# 05021002_GPIO_s.net
KiCad netlist of a schematic drawn in Altium Designer
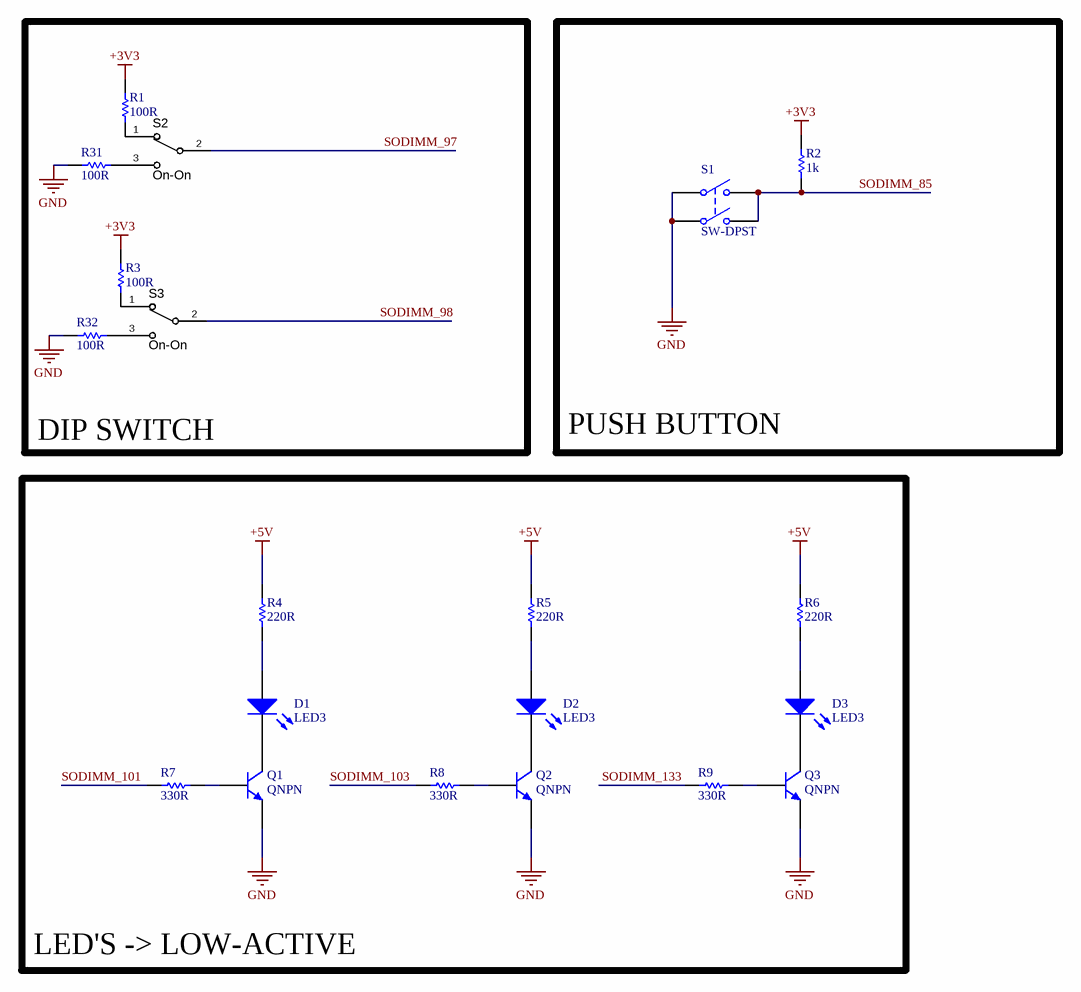
[diagram p0: 05021002_GPIO's.SchDoc]

(export (version "E")
  (design (tool "Eeschema 10.0.6"))
  (components
    (comp (ref "D1")
      (value "LED3")
      (footprint "LED-0805-K")
      (description "Typical BLUE SiC LED")
      (fields (field (name "PUBLISHER") "Altium Limited"))
      (libsource (lib "Miscellaneous Devices") (part "LED3"))
    )
    (comp (ref "D2")
      (value "LED3")
      (footprint "LED-0805-K")
      (description "Typical BLUE SiC LED")
      (fields (field (name "PUBLISHER") "Altium Limited"))
      (libsource (lib "Miscellaneous Devices") (part "LED3"))
    )
    (comp (ref "D3")
      (value "LED3")
      (footprint "LED-0805-K")
      (description "Typical BLUE SiC LED")
      (fields (field (name "PUBLISHER") "Altium Limited"))
      (libsource (lib "Miscellaneous Devices") (part "LED3"))
    )
    (comp (ref "Q1")
      (value "QNPN")
      (footprint "SOT-23")
      (description "NPN Bipolar Transistor")
      (fields (field (name "PUBLISHER") "Altium Limited"))
      (libsource (lib "Miscellaneous Devices") (part "QNPN"))
    )
    (comp (ref "Q2")
      (value "QNPN")
      (footprint "SOT-23")
      (description "NPN Bipolar Transistor")
      (fields (field (name "PUBLISHER") "Altium Limited"))
      (libsource (lib "Miscellaneous Devices") (part "QNPN"))
    )
    (comp (ref "Q3")
      (value "QNPN")
      (footprint "SOT-23")
      (description "NPN Bipolar Transistor")
      (fields (field (name "PUBLISHER") "Altium Limited"))
      (libsource (lib "Miscellaneous Devices") (part "QNPN"))
    )
    (comp (ref "R1")
      (value "100R")
      (footprint "0805")
      (libsource (lib "resistor_smd_gen") (part "resistor_gen"))
    )
    (comp (ref "R2")
      (value "1k")
      (footprint "0805")
      (libsource (lib "resistor_smd_gen") (part "resistor_gen"))
    )
    (comp (ref "R3")
      (value "100R")
      (footprint "0805")
      (libsource (lib "resistor_smd_gen") (part "resistor_gen"))
    )
    (comp (ref "R4")
      (value "220R")
      (footprint "0805")
      (libsource (lib "resistor_smd_gen") (part "resistor_gen"))
    )
    (comp (ref "R5")
      (value "220R")
      (footprint "0805")
      (libsource (lib "resistor_smd_gen") (part "resistor_gen"))
    )
    (comp (ref "R6")
      (value "220R")
      (footprint "0805")
      (libsource (lib "resistor_smd_gen") (part "resistor_gen"))
    )
    (comp (ref "R7")
      (value "330R")
      (footprint "0805")
      (libsource (lib "resistor_smd_gen") (part "resistor_gen"))
    )
    (comp (ref "R8")
      (value "330R")
      (footprint "0805")
      (libsource (lib "resistor_smd_gen") (part "resistor_gen"))
    )
    (comp (ref "R9")
      (value "330R")
      (footprint "0805")
      (libsource (lib "resistor_smd_gen") (part "resistor_gen"))
    )
    (comp (ref "R31")
      (value "100R")
      (footprint "0805")
      (libsource (lib "resistor_smd_gen") (part "resistor_gen"))
    )
    (comp (ref "R32")
      (value "100R")
      (footprint "0805")
      (libsource (lib "resistor_smd_gen") (part "resistor_gen"))
    )
    (comp (ref "S1")
      (value "SW-DPST")
      (footprint "430182080816")
      (description "Double-Pole, Single-Throw Switch")
      (fields (field (name "PUBLISHER") "Altium Limited"))
      (libsource (lib "Miscellaneous Devices") (part "SW-DPST"))
    )
    (comp (ref "S2")
      (value "ON-ON")
      (footprint "SWITCH_SPDT_SLIDER")
      (description "Switch THD vertical toggle SPDT")
      (fields (field (name "SWITCH FUNCTION") "On-On"))
      (libsource (lib "PBL - Switches") (part "SW_THD_SPDT_On-On"))
    )
    (comp (ref "S3")
      (value "ON-ON")
      (footprint "SWITCH_SPDT_SLIDER")
      (description "Switch THD vertical toggle SPDT")
      (fields (field (name "SWITCH FUNCTION") "On-On"))
      (libsource (lib "PBL - Switches") (part "SW_THD_SPDT_On-On"))
    )
  )
  (nets
    (net (code "1") (name "+3V3") (class "Default")
      (node (ref "R1") (pin "2") (pinfunction "2_2") (pintype "passive"))
      (node (ref "R2") (pin "2") (pinfunction "2_2") (pintype "passive"))
      (node (ref "R3") (pin "2") (pinfunction "2_2") (pintype "passive"))
    )
    (net (code "2") (name "+5V") (class "Default")
      (node (ref "R4") (pin "2") (pinfunction "2_2") (pintype "passive"))
      (node (ref "R5") (pin "2") (pinfunction "2_2") (pintype "passive"))
      (node (ref "R6") (pin "2") (pinfunction "2_2") (pintype "passive"))
    )
    (net (code "3") (name "/SODIMM_85") (class "Default")
      (node (ref "R2") (pin "1") (pinfunction "1_1") (pintype "passive"))
      (node (ref "S1") (pin "2") (pinfunction "NO1_2") (pintype "passive"))
      (node (ref "S1") (pin "4") (pinfunction "NO2_4") (pintype "passive"))
    )
    (net (code "4") (name "/SODIMM_97") (class "Default")
      (node (ref "S2") (pin "2") (pinfunction "2_2") (pintype "passive"))
    )
    (net (code "5") (name "/SODIMM_98") (class "Default")
      (node (ref "S3") (pin "2") (pinfunction "2_2") (pintype "passive"))
    )
    (net (code "6") (name "/SODIMM_101") (class "Default")
      (node (ref "R7") (pin "1") (pinfunction "1_1") (pintype "passive"))
    )
    (net (code "7") (name "/SODIMM_103") (class "Default")
      (node (ref "R8") (pin "1") (pinfunction "1_1") (pintype "passive"))
    )
    (net (code "8") (name "/SODIMM_133") (class "Default")
      (node (ref "R9") (pin "1") (pinfunction "1_1") (pintype "passive"))
    )
    (net (code "9") (name "GND") (class "Default")
      (node (ref "Q1") (pin "3") (pinfunction "E_3") (pintype "passive"))
      (node (ref "Q2") (pin "3") (pinfunction "E_3") (pintype "passive"))
      (node (ref "Q3") (pin "3") (pinfunction "E_3") (pintype "passive"))
      (node (ref "R31") (pin "2") (pinfunction "2_2") (pintype "passive"))
      (node (ref "R32") (pin "2") (pinfunction "2_2") (pintype "passive"))
      (node (ref "S1") (pin "1") (pinfunction "COMMON1_1") (pintype "passive"))
      (node (ref "S1") (pin "3") (pinfunction "COMMON2_3") (pintype "passive"))
    )
    (net (code "10") (name "Net-(D1-A)") (class "Default")
      (node (ref "D1") (pin "1") (pinfunction "A_1") (pintype "passive"))
      (node (ref "R4") (pin "1") (pinfunction "1_1") (pintype "passive"))
    )
    (net (code "11") (name "Net-(D1-K)") (class "Default")
      (node (ref "D1") (pin "2") (pinfunction "K_2") (pintype "passive"))
      (node (ref "Q1") (pin "1") (pinfunction "C_1") (pintype "passive"))
    )
    (net (code "12") (name "Net-(D2-A)") (class "Default")
      (node (ref "D2") (pin "1") (pinfunction "A_1") (pintype "passive"))
      (node (ref "R5") (pin "1") (pinfunction "1_1") (pintype "passive"))
    )
    (net (code "13") (name "Net-(D2-K)") (class "Default")
      (node (ref "D2") (pin "2") (pinfunction "K_2") (pintype "passive"))
      (node (ref "Q2") (pin "1") (pinfunction "C_1") (pintype "passive"))
    )
    (net (code "14") (name "Net-(D3-A)") (class "Default")
      (node (ref "D3") (pin "1") (pinfunction "A_1") (pintype "passive"))
      (node (ref "R6") (pin "1") (pinfunction "1_1") (pintype "passive"))
    )
    (net (code "15") (name "Net-(D3-K)") (class "Default")
      (node (ref "D3") (pin "2") (pinfunction "K_2") (pintype "passive"))
      (node (ref "Q3") (pin "1") (pinfunction "C_1") (pintype "passive"))
    )
    (net (code "16") (name "Net-(Q1-B)") (class "Default")
      (node (ref "Q1") (pin "2") (pinfunction "B_2") (pintype "passive"))
      (node (ref "R7") (pin "2") (pinfunction "2_2") (pintype "passive"))
    )
    (net (code "17") (name "Net-(Q2-B)") (class "Default")
      (node (ref "Q2") (pin "2") (pinfunction "B_2") (pintype "passive"))
      (node (ref "R8") (pin "2") (pinfunction "2_2") (pintype "passive"))
    )
    (net (code "18") (name "Net-(Q3-B)") (class "Default")
      (node (ref "Q3") (pin "2") (pinfunction "B_2") (pintype "passive"))
      (node (ref "R9") (pin "2") (pinfunction "2_2") (pintype "passive"))
    )
    (net (code "19") (name "Net-(R1-Pad1)") (class "Default")
      (node (ref "R1") (pin "1") (pinfunction "1_1") (pintype "passive"))
      (node (ref "S2") (pin "1") (pinfunction "1_1") (pintype "passive"))
    )
    (net (code "20") (name "Net-(R3-Pad1)") (class "Default")
      (node (ref "R3") (pin "1") (pinfunction "1_1") (pintype "passive"))
      (node (ref "S3") (pin "1") (pinfunction "1_1") (pintype "passive"))
    )
    (net (code "21") (name "Net-(R31-Pad1)") (class "Default")
      (node (ref "R31") (pin "1") (pinfunction "1_1") (pintype "passive"))
      (node (ref "S2") (pin "3") (pinfunction "3_3") (pintype "passive"))
    )
    (net (code "22") (name "Net-(R32-Pad1)") (class "Default")
      (node (ref "R32") (pin "1") (pinfunction "1_1") (pintype "passive"))
      (node (ref "S3") (pin "3") (pinfunction "3_3") (pintype "passive"))
    )
  )
)
